# 05_IO_CONN.net
KiCad netlist of a schematic drawn in Altium Designer
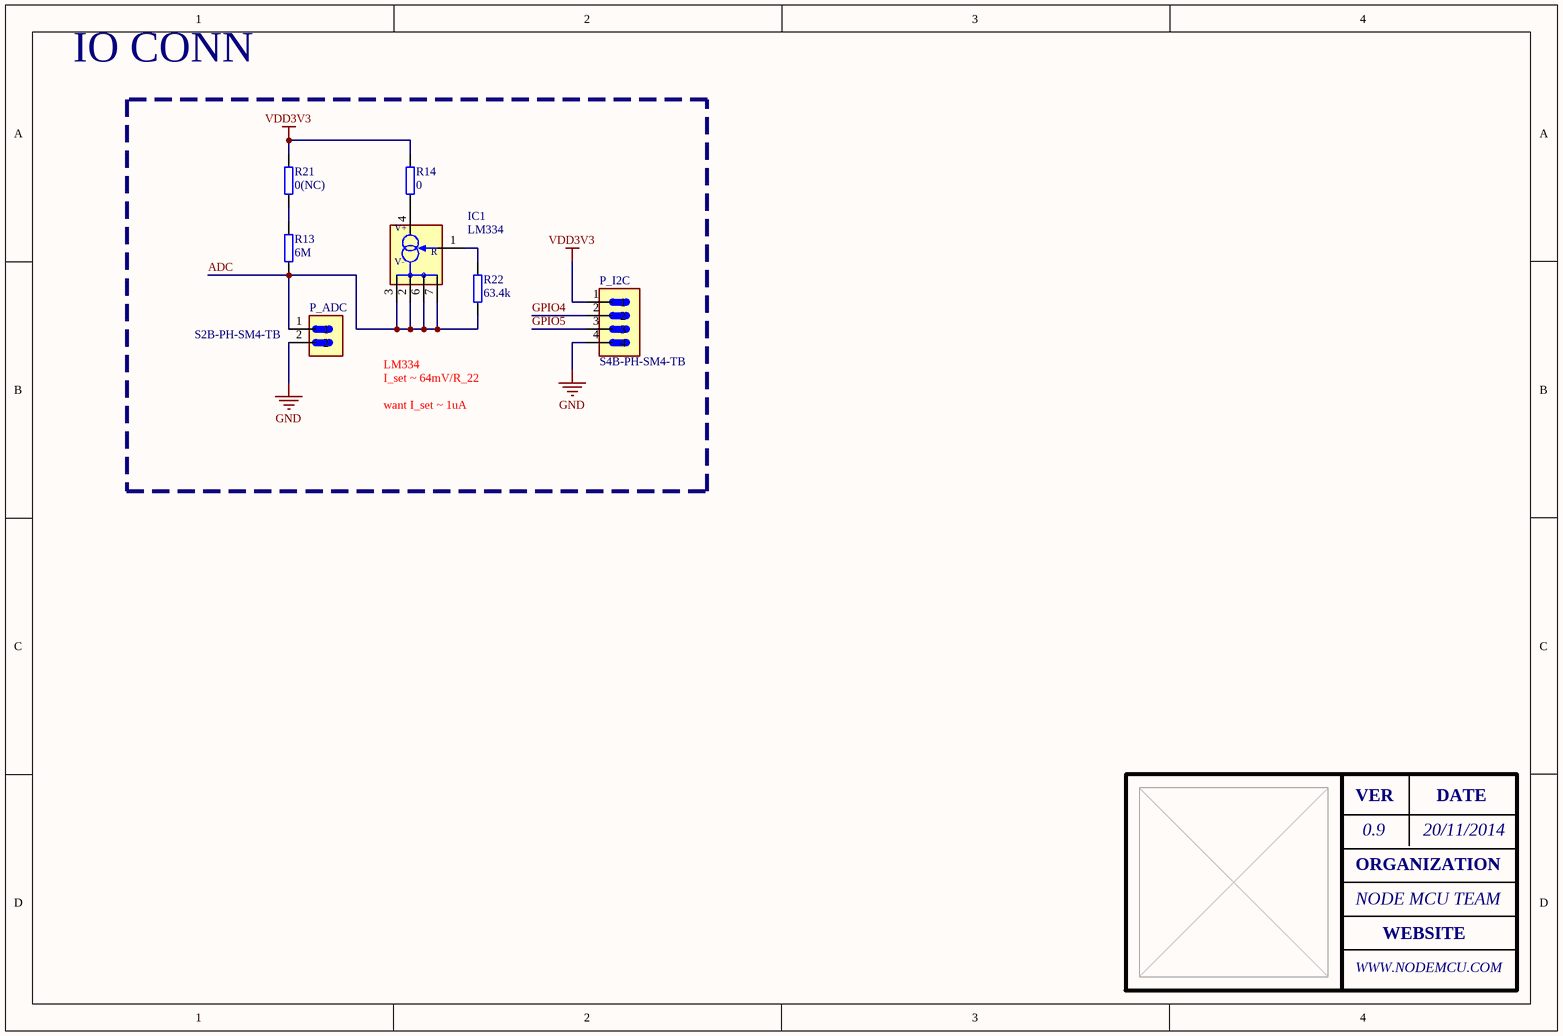
[diagram p0: 05_IO_CONN.SchDoc]

(export (version "E")
  (design (tool "Eeschema 10.0.6"))
  (components
    (comp (ref "IC1")
      (value "LM334")
      (footprint "SO08")
      (description "Current Source Regulator Adjustable 8-SOIC")
      (fields (field (name "MF") "Texas Instruments"))
      (libsource (lib "cupmat") (part "LM334"))
    )
    (comp (ref "P_ADC")
      (value "S2B-PH-SM4-TB")
      (footprint "JST_S2B-PH-SM4-TB")
      (description "Connector Header Surface Mount, Right Angle 2 position 0.079 _2.00mm_")
      (fields (field (name "MF") "JST Sales"))
      (libsource (lib "cupmat") (part "S2B-PH-SM4-TB"))
    )
    (comp (ref "P_I2C")
      (value "S4B-PH-SM4-TB")
      (footprint "JST_S4B-PH-SM4-TB")
      (description "Connector Header Surface Mount, Right Angle 4 position 0.079 _2.00mm_")
      (fields (field (name "MF") "JST Sales"))
      (libsource (lib "cupmat") (part "S4B-PH-SM4-TB"))
    )
    (comp (ref "R13")
      (value "6M")
      (footprint "SMT_R_0402")
      (description "Surface mount resistor 0402")
      (libsource (lib "cupmat") (part "SMT_R_0402"))
    )
    (comp (ref "R14")
      (value "0")
      (footprint "SMT_R_0402")
      (description "Surface mount resistor 0402")
      (libsource (lib "cupmat") (part "SMT_R_0402"))
    )
    (comp (ref "R21")
      (value "0(NC)")
      (footprint "SMT_R_0402")
      (description "Surface mount resistor 0402")
      (libsource (lib "cupmat") (part "SMT_R_0402"))
    )
    (comp (ref "R22")
      (value "63.4k")
      (footprint "SMT_R_0402")
      (description "Surface mount resistor 0402")
      (libsource (lib "cupmat") (part "SMT_R_0402"))
    )
  )
  (nets
    (net (code "1") (name "/ADC") (class "Default")
      (node (ref "IC1") (pin "2") (pinfunction "V-_2") (pintype "passive"))
      (node (ref "IC1") (pin "3") (pinfunction "V-@1_3") (pintype "passive"))
      (node (ref "IC1") (pin "6") (pinfunction "V-@2_6") (pintype "passive"))
      (node (ref "IC1") (pin "7") (pinfunction "V-@3_7") (pintype "passive"))
      (node (ref "P_ADC") (pin "1") (pinfunction "1_1") (pintype "passive"))
      (node (ref "R13") (pin "1") (pinfunction "1_1") (pintype "passive"))
      (node (ref "R22") (pin "1") (pinfunction "1_1") (pintype "passive"))
    )
    (net (code "2") (name "/GPIO4") (class "Default")
      (node (ref "P_I2C") (pin "2") (pinfunction "2_2") (pintype "passive"))
    )
    (net (code "3") (name "/GPIO5") (class "Default")
      (node (ref "P_I2C") (pin "3") (pinfunction "3_3") (pintype "passive"))
    )
    (net (code "4") (name "GND") (class "Default")
      (node (ref "P_ADC") (pin "2") (pinfunction "2_2") (pintype "passive"))
      (node (ref "P_I2C") (pin "4") (pinfunction "4_4") (pintype "passive"))
    )
    (net (code "5") (name "Net-(IC1-R)") (class "Default")
      (node (ref "IC1") (pin "1") (pinfunction "R_1") (pintype "passive"))
      (node (ref "R22") (pin "2") (pinfunction "2_2") (pintype "passive"))
    )
    (net (code "6") (name "Net-(IC1-V+)") (class "Default")
      (node (ref "IC1") (pin "4") (pinfunction "V+_4") (pintype "passive"))
      (node (ref "R14") (pin "1") (pinfunction "1_1") (pintype "passive"))
    )
    (net (code "7") (name "Net-(R13-Pad2)") (class "Default")
      (node (ref "R13") (pin "2") (pinfunction "2_2") (pintype "passive"))
      (node (ref "R21") (pin "1") (pinfunction "1_1") (pintype "passive"))
    )
    (net (code "8") (name "VDD3V3") (class "Default")
      (node (ref "P_I2C") (pin "1") (pinfunction "1_1") (pintype "passive"))
      (node (ref "R14") (pin "2") (pinfunction "2_2") (pintype "passive"))
      (node (ref "R21") (pin "2") (pinfunction "2_2") (pintype "passive"))
    )
  )
)
